# rohan.net
KiCad netlist of a schematic drawn in EAGLE
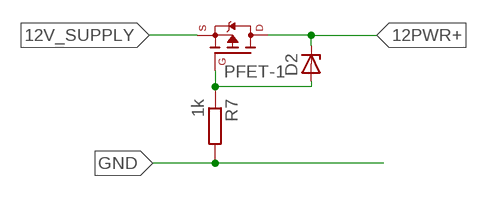
[diagram p0: schematic, sheet 1]

(export (version "E")
  (design (tool "Eeschema 10.0.6"))
  (components
    (comp (ref "D2")
      (value "1SMA5925BT3G")
      (footprint "eagle-import:DO214AC")
      (fields (field (name "MF") "ON Semiconductor"))
      (libsource (lib "eagle-import") (part "1SMA59BT3G25"))
    )
    (comp (ref "PFET-1")
      (value "FQP47P06NORMAL")
      (footprint "eagle-import:FQP47P06-NORMAL")
      (libsource (lib "eagle-import") (part "FQP47P06NORMAL"))
    )
    (comp (ref "R7")
      (value "1k")
      (footprint "eagle-import:R0603")
      (libsource (lib "eagle-import") (part "R-EU_R0603"))
    )
  )
  (nets
    (net (code "1") (name "12PWR+") (class "Default")
      (node (ref "D2") (pin "C") (pinfunction "C_C") (pintype "passive"))
      (node (ref "PFET-1") (pin "2") (pinfunction "D_2") (pintype "passive"))
    )
    (net (code "2") (name "12V_SUPPLY") (class "Default")
      (node (ref "PFET-1") (pin "3") (pinfunction "S_3") (pintype "passive"))
    )
    (net (code "3") (name "GND") (class "Default")
      (node (ref "R7") (pin "2") (pinfunction "2_2") (pintype "passive"))
    )
    (net (code "4") (name "Net-(PFET-1-G)") (class "Default")
      (node (ref "D2") (pin "A") (pinfunction "A_A") (pintype "passive"))
      (node (ref "PFET-1") (pin "1") (pinfunction "G_1") (pintype "passive"))
      (node (ref "R7") (pin "1") (pinfunction "1_1") (pintype "passive"))
    )
  )
)
